# TRC_main1_0_0.net
KiCad netlist of a schematic drawn in EAGLE
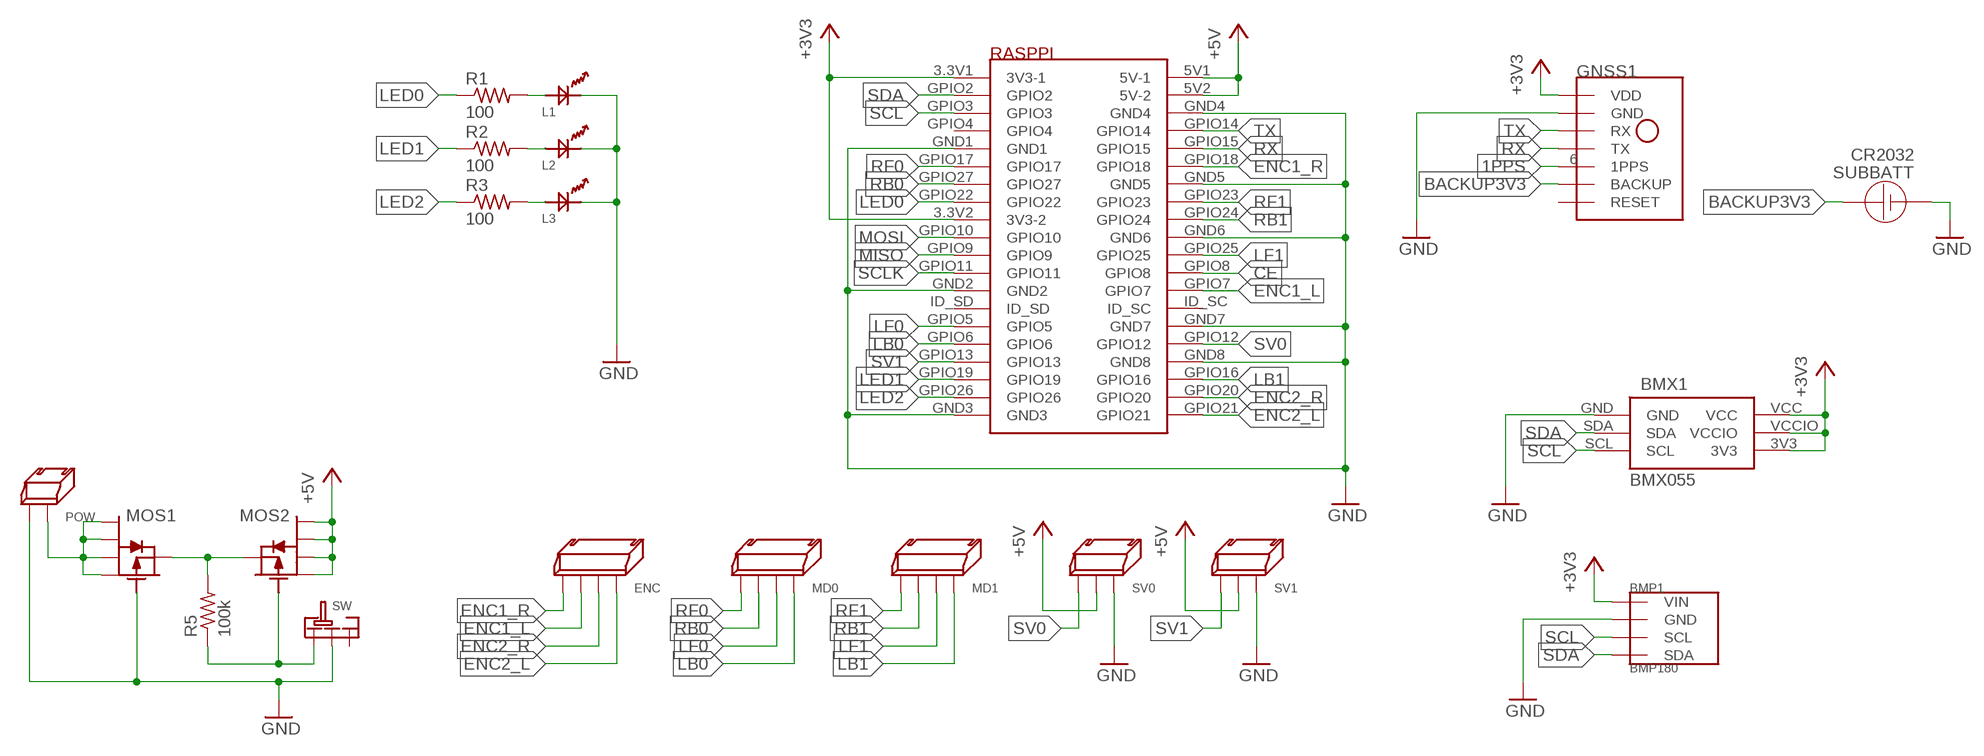
[diagram p0: schematic, sheet 1]

(export (version "E")
  (design (tool "Eeschema 10.0.6"))
  (components
    (comp (ref "BMP1")
      (value "BMP180")
      (footprint "eagle-import:GY-68")
      (libsource (lib "eagle-import") (part "BMP180"))
    )
    (comp (ref "BMX1")
      (value "BMX055")
      (footprint "eagle-import:BMX055")
      (libsource (lib "eagle-import") (part "BMX055"))
    )
    (comp (ref "ENC")
      (value "4PIN_SIDE")
      (footprint "eagle-import:4PIN_SIDE")
      (libsource (lib "eagle-import") (part "4PIN_SIDE"))
    )
    (comp (ref "GNSS1")
      (value "GYSFDMAXB")
      (footprint "eagle-import:GYSFDMAXB")
      (libsource (lib "eagle-import") (part "GYSFDMAXB"))
    )
    (comp (ref "L1")
      (value "OSXX1608C1A")
      (footprint "eagle-import:OSXX1608C1A")
      (libsource (lib "eagle-import") (part "OSXX1608C1A"))
    )
    (comp (ref "L2")
      (value "OSXX1608C1A")
      (footprint "eagle-import:OSXX1608C1A")
      (libsource (lib "eagle-import") (part "OSXX1608C1A"))
    )
    (comp (ref "L3")
      (value "OSXX1608C1A")
      (footprint "eagle-import:OSXX1608C1A")
      (libsource (lib "eagle-import") (part "OSXX1608C1A"))
    )
    (comp (ref "MD0")
      (value "4PIN_SIDE")
      (footprint "eagle-import:4PIN_SIDE")
      (libsource (lib "eagle-import") (part "4PIN_SIDE"))
    )
    (comp (ref "MD1")
      (value "4PIN_SIDE")
      (footprint "eagle-import:4PIN_SIDE")
      (libsource (lib "eagle-import") (part "4PIN_SIDE"))
    )
    (comp (ref "MOS1")
      (value "PCH_SSM6J808R")
      (footprint "eagle-import:SSM6J808R")
      (libsource (lib "eagle-import") (part "PCH_SSM6J808R"))
    )
    (comp (ref "MOS2")
      (value "PCH_SSM6J808R")
      (footprint "eagle-import:SSM6J808R")
      (libsource (lib "eagle-import") (part "PCH_SSM6J808R"))
    )
    (comp (ref "POW")
      (value "2PIN_SIDE")
      (footprint "eagle-import:2PIN_SIDE")
      (libsource (lib "eagle-import") (part "2PIN_SIDE"))
    )
    (comp (ref "R1")
      (value "100")
      (footprint "eagle-import:R0603")
      (libsource (lib "eagle-import") (part "R-US_R0603"))
    )
    (comp (ref "R2")
      (value "100")
      (footprint "eagle-import:R0603")
      (libsource (lib "eagle-import") (part "R-US_R0603"))
    )
    (comp (ref "R3")
      (value "100")
      (footprint "eagle-import:R0603")
      (libsource (lib "eagle-import") (part "R-US_R0603"))
    )
    (comp (ref "R5")
      (value "100k")
      (footprint "eagle-import:R0603")
      (libsource (lib "eagle-import") (part "R-US_R0603"))
    )
    (comp (ref "RASPPI")
      (value "RASPBERYPIZEROW")
      (footprint "eagle-import:RASPBERYPIZEROW")
      (libsource (lib "eagle-import") (part "RASPBERYPIZEROW"))
    )
    (comp (ref "SUBBATT")
      (value "CR2032")
      (footprint "eagle-import:CR2032")
      (libsource (lib "eagle-import") (part "CR2032"))
    )
    (comp (ref "SV0")
      (value "3PIN_SIDE")
      (footprint "eagle-import:3PIN_SIDE")
      (libsource (lib "eagle-import") (part "3PIN_SIDE"))
    )
    (comp (ref "SV1")
      (value "3PIN_SIDE")
      (footprint "eagle-import:3PIN_SIDE")
      (libsource (lib "eagle-import") (part "3PIN_SIDE"))
    )
    (comp (ref "SW")
      (value "SRIDE_SWITCH")
      (footprint "eagle-import:SRIDE_SWITCH")
      (libsource (lib "eagle-import") (part "SRIDE_SWITCH"))
    )
  )
  (nets
    (net (code "1") (name "+3V3") (class "Default")
      (node (ref "BMP1") (pin "P1") (pinfunction "VIN_P1") (pintype "bidirectional"))
      (node (ref "BMX1") (pin "3V3") (pinfunction "3V3_3V3") (pintype "power_in"))
      (node (ref "BMX1") (pin "VCC") (pinfunction "VCC_VCC") (pintype "power_in"))
      (node (ref "BMX1") (pin "VCCIO") (pinfunction "VCCIO_VCCIO") (pintype "power_in"))
      (node (ref "GNSS1") (pin "16") (pinfunction "VDD_16") (pintype "bidirectional"))
      (node (ref "RASPPI") (pin "3.3V1") (pinfunction "3V3-1_3.3V1") (pintype "bidirectional"))
      (node (ref "RASPPI") (pin "3.3V2") (pinfunction "3V3-2_3.3V2") (pintype "bidirectional"))
    )
    (net (code "2") (name "+5V") (class "Default")
      (node (ref "MOS2") (pin "1") (pinfunction "1_1") (pintype "bidirectional"))
      (node (ref "MOS2") (pin "2") (pinfunction "2_2") (pintype "bidirectional"))
      (node (ref "MOS2") (pin "5") (pinfunction "5_5") (pintype "bidirectional"))
      (node (ref "MOS2") (pin "6") (pinfunction "6_6") (pintype "bidirectional"))
      (node (ref "RASPPI") (pin "5V1") (pinfunction "5V-1_5V1") (pintype "bidirectional"))
      (node (ref "RASPPI") (pin "5V2") (pinfunction "5V-2_5V2") (pintype "bidirectional"))
      (node (ref "SV0") (pin "P$1") (pinfunction "P$1_P$1") (pintype "bidirectional"))
      (node (ref "SV1") (pin "P$1") (pinfunction "P$1_P$1") (pintype "bidirectional"))
    )
    (net (code "3") (name "1PPS") (class "Default")
      (node (ref "GNSS1") (pin "6") (pinfunction "1PPS_6") (pintype "bidirectional"))
    )
    (net (code "4") (name "BACKUP3V3") (class "Default")
      (node (ref "GNSS1") (pin "14") (pinfunction "BACKUP_14") (pintype "bidirectional"))
      (node (ref "SUBBATT") (pin "VCC") (pinfunction "VCC_VCC") (pintype "bidirectional"))
      (node (ref "SUBBATT") (pin "VCC2") (pinfunction "VCC_VCC2") (pintype "bidirectional"))
    )
    (net (code "5") (name "CE") (class "Default")
      (node (ref "RASPPI") (pin "GPIO8") (pinfunction "GPIO8_GPIO8") (pintype "bidirectional"))
    )
    (net (code "6") (name "ENC1_L") (class "Default")
      (node (ref "ENC") (pin "P$1") (pinfunction "P$1_P$1") (pintype "bidirectional"))
      (node (ref "RASPPI") (pin "GPIO7") (pinfunction "GPIO7_GPIO7") (pintype "bidirectional"))
    )
    (net (code "7") (name "ENC1_R") (class "Default")
      (node (ref "ENC") (pin "P$2") (pinfunction "P$2_P$2") (pintype "bidirectional"))
      (node (ref "RASPPI") (pin "GPIO18") (pinfunction "GPIO18_GPIO18") (pintype "bidirectional"))
    )
    (net (code "8") (name "ENC2_L") (class "Default")
      (node (ref "ENC") (pin "P$4") (pinfunction "P$4_P$4") (pintype "bidirectional"))
      (node (ref "RASPPI") (pin "GPIO21") (pinfunction "GPIO21_GPIO21") (pintype "bidirectional"))
    )
    (net (code "9") (name "ENC2_R") (class "Default")
      (node (ref "ENC") (pin "P$3") (pinfunction "P$3_P$3") (pintype "bidirectional"))
      (node (ref "RASPPI") (pin "GPIO20") (pinfunction "GPIO20_GPIO20") (pintype "bidirectional"))
    )
    (net (code "10") (name "GND") (class "Default")
      (node (ref "BMP1") (pin "P2") (pinfunction "GND_P2") (pintype "bidirectional"))
      (node (ref "BMX1") (pin "GND") (pinfunction "GND_GND") (pintype "power_in"))
      (node (ref "GNSS1") (pin "1") (pinfunction "GND_1") (pintype "bidirectional"))
      (node (ref "GNSS1") (pin "10") (pinfunction "GND_10") (pintype "bidirectional"))
      (node (ref "GNSS1") (pin "12") (pinfunction "GND_12") (pintype "bidirectional"))
      (node (ref "GNSS1") (pin "19") (pinfunction "GND_19") (pintype "bidirectional"))
      (node (ref "GNSS1") (pin "2") (pinfunction "GND_2") (pintype "bidirectional"))
      (node (ref "GNSS1") (pin "20") (pinfunction "GND_20") (pintype "bidirectional"))
      (node (ref "GNSS1") (pin "7") (pinfunction "GND_7") (pintype "bidirectional"))
      (node (ref "L1") (pin "CT") (pinfunction "CT_CT") (pintype "bidirectional"))
      (node (ref "L2") (pin "CT") (pinfunction "CT_CT") (pintype "bidirectional"))
      (node (ref "L3") (pin "CT") (pinfunction "CT_CT") (pintype "bidirectional"))
      (node (ref "MOS1") (pin "3") (pinfunction "3_3") (pintype "bidirectional"))
      (node (ref "POW") (pin "P$2") (pinfunction "P$2_P$2") (pintype "bidirectional"))
      (node (ref "RASPPI") (pin "GND1") (pinfunction "GND1_GND1") (pintype "bidirectional"))
      (node (ref "RASPPI") (pin "GND2") (pinfunction "GND2_GND2") (pintype "bidirectional"))
      (node (ref "RASPPI") (pin "GND3") (pinfunction "GND3_GND3") (pintype "bidirectional"))
      (node (ref "RASPPI") (pin "GND4") (pinfunction "GND4_GND4") (pintype "bidirectional"))
      (node (ref "RASPPI") (pin "GND5") (pinfunction "GND5_GND5") (pintype "bidirectional"))
      (node (ref "RASPPI") (pin "GND6") (pinfunction "GND6_GND6") (pintype "bidirectional"))
      (node (ref "RASPPI") (pin "GND7") (pinfunction "GND7_GND7") (pintype "bidirectional"))
      (node (ref "RASPPI") (pin "GND8") (pinfunction "GND8_GND8") (pintype "bidirectional"))
      (node (ref "SUBBATT") (pin "GND") (pinfunction "GND_GND") (pintype "bidirectional"))
      (node (ref "SV0") (pin "P$3") (pinfunction "P$3_P$3") (pintype "bidirectional"))
      (node (ref "SV1") (pin "P$3") (pinfunction "P$3_P$3") (pintype "bidirectional"))
      (node (ref "SW") (pin "LR") (pinfunction "LR_LR") (pintype "bidirectional"))
    )
    (net (code "11") (name "LB0") (class "Default")
      (node (ref "MD0") (pin "P$4") (pinfunction "P$4_P$4") (pintype "bidirectional"))
      (node (ref "RASPPI") (pin "GPIO6") (pinfunction "GPIO6_GPIO6") (pintype "bidirectional"))
    )
    (net (code "12") (name "LB1") (class "Default")
      (node (ref "MD1") (pin "P$4") (pinfunction "P$4_P$4") (pintype "bidirectional"))
      (node (ref "RASPPI") (pin "GPIO16") (pinfunction "GPIO16_GPIO16") (pintype "bidirectional"))
    )
    (net (code "13") (name "LED0") (class "Default")
      (node (ref "R1") (pin "1") (pinfunction "1_1") (pintype "passive"))
      (node (ref "RASPPI") (pin "GPIO22") (pinfunction "GPIO22_GPIO22") (pintype "bidirectional"))
    )
    (net (code "14") (name "LED1") (class "Default")
      (node (ref "R2") (pin "1") (pinfunction "1_1") (pintype "passive"))
      (node (ref "RASPPI") (pin "GPIO19") (pinfunction "GPIO19_GPIO19") (pintype "bidirectional"))
    )
    (net (code "15") (name "LED2") (class "Default")
      (node (ref "R3") (pin "1") (pinfunction "1_1") (pintype "passive"))
      (node (ref "RASPPI") (pin "GPIO26") (pinfunction "GPIO26_GPIO26") (pintype "bidirectional"))
    )
    (net (code "16") (name "LF0") (class "Default")
      (node (ref "MD0") (pin "P$3") (pinfunction "P$3_P$3") (pintype "bidirectional"))
      (node (ref "RASPPI") (pin "GPIO5") (pinfunction "GPIO5_GPIO5") (pintype "bidirectional"))
    )
    (net (code "17") (name "LF1") (class "Default")
      (node (ref "MD1") (pin "P$3") (pinfunction "P$3_P$3") (pintype "bidirectional"))
      (node (ref "RASPPI") (pin "GPIO25") (pinfunction "GPIO25_GPIO25") (pintype "bidirectional"))
    )
    (net (code "18") (name "MISO") (class "Default")
      (node (ref "RASPPI") (pin "GPIO9") (pinfunction "GPIO9_GPIO9") (pintype "bidirectional"))
    )
    (net (code "19") (name "MOSI") (class "Default")
      (node (ref "RASPPI") (pin "GPIO10") (pinfunction "GPIO10_GPIO10") (pintype "bidirectional"))
    )
    (net (code "20") (name "Net-(L1-PadAN)") (class "Default")
      (node (ref "L1") (pin "AN") (pinfunction "AN_AN") (pintype "bidirectional"))
      (node (ref "R1") (pin "2") (pinfunction "2_2") (pintype "passive"))
    )
    (net (code "21") (name "Net-(L2-PadAN)") (class "Default")
      (node (ref "L2") (pin "AN") (pinfunction "AN_AN") (pintype "bidirectional"))
      (node (ref "R2") (pin "2") (pinfunction "2_2") (pintype "passive"))
    )
    (net (code "22") (name "Net-(L3-PadAN)") (class "Default")
      (node (ref "L3") (pin "AN") (pinfunction "AN_AN") (pintype "bidirectional"))
      (node (ref "R3") (pin "2") (pinfunction "2_2") (pintype "passive"))
    )
    (net (code "23") (name "Net-(MOS1-Pad1)") (class "Default")
      (node (ref "MOS1") (pin "1") (pinfunction "1_1") (pintype "bidirectional"))
      (node (ref "MOS1") (pin "2") (pinfunction "2_2") (pintype "bidirectional"))
      (node (ref "MOS1") (pin "5") (pinfunction "5_5") (pintype "bidirectional"))
      (node (ref "MOS1") (pin "6") (pinfunction "6_6") (pintype "bidirectional"))
      (node (ref "POW") (pin "P$1") (pinfunction "P$1_P$1") (pintype "bidirectional"))
    )
    (net (code "24") (name "Net-(MOS1-Pad4)") (class "Default")
      (node (ref "MOS1") (pin "4") (pinfunction "4_4") (pintype "bidirectional"))
      (node (ref "MOS2") (pin "4") (pinfunction "4_4") (pintype "bidirectional"))
      (node (ref "R5") (pin "2") (pinfunction "2_2") (pintype "passive"))
    )
    (net (code "25") (name "Net-(MOS2-Pad3)") (class "Default")
      (node (ref "MOS2") (pin "3") (pinfunction "3_3") (pintype "bidirectional"))
      (node (ref "R5") (pin "1") (pinfunction "1_1") (pintype "passive"))
      (node (ref "SW") (pin "L") (pinfunction "L_L") (pintype "bidirectional"))
    )
    (net (code "26") (name "RB0") (class "Default")
      (node (ref "MD0") (pin "P$1") (pinfunction "P$1_P$1") (pintype "bidirectional"))
      (node (ref "RASPPI") (pin "GPIO27") (pinfunction "GPIO27_GPIO27") (pintype "bidirectional"))
    )
    (net (code "27") (name "RB1") (class "Default")
      (node (ref "MD1") (pin "P$1") (pinfunction "P$1_P$1") (pintype "bidirectional"))
      (node (ref "RASPPI") (pin "GPIO24") (pinfunction "GPIO24_GPIO24") (pintype "bidirectional"))
    )
    (net (code "28") (name "RF0") (class "Default")
      (node (ref "MD0") (pin "P$2") (pinfunction "P$2_P$2") (pintype "bidirectional"))
      (node (ref "RASPPI") (pin "GPIO17") (pinfunction "GPIO17_GPIO17") (pintype "bidirectional"))
    )
    (net (code "29") (name "RF1") (class "Default")
      (node (ref "MD1") (pin "P$2") (pinfunction "P$2_P$2") (pintype "bidirectional"))
      (node (ref "RASPPI") (pin "GPIO23") (pinfunction "GPIO23_GPIO23") (pintype "bidirectional"))
    )
    (net (code "30") (name "RX") (class "Default")
      (node (ref "GNSS1") (pin "5") (pinfunction "TX_5") (pintype "bidirectional"))
      (node (ref "RASPPI") (pin "GPIO15") (pinfunction "GPIO15_GPIO15") (pintype "bidirectional"))
    )
    (net (code "31") (name "SCL") (class "Default")
      (node (ref "BMP1") (pin "P3") (pinfunction "SCL_P3") (pintype "bidirectional"))
      (node (ref "BMX1") (pin "SCL") (pinfunction "SCL_SCL") (pintype "bidirectional"))
      (node (ref "RASPPI") (pin "GPIO3") (pinfunction "GPIO3_GPIO3") (pintype "bidirectional"))
    )
    (net (code "32") (name "SCLK") (class "Default")
      (node (ref "RASPPI") (pin "GPIO11") (pinfunction "GPIO11_GPIO11") (pintype "bidirectional"))
    )
    (net (code "33") (name "SDA") (class "Default")
      (node (ref "BMP1") (pin "P4") (pinfunction "SDA_P4") (pintype "bidirectional"))
      (node (ref "BMX1") (pin "SDA") (pinfunction "SDA_SDA") (pintype "bidirectional"))
      (node (ref "RASPPI") (pin "GPIO2") (pinfunction "GPIO2_GPIO2") (pintype "bidirectional"))
    )
    (net (code "34") (name "SV0") (class "Default")
      (node (ref "RASPPI") (pin "GPIO12") (pinfunction "GPIO12_GPIO12") (pintype "bidirectional"))
      (node (ref "SV0") (pin "P$2") (pinfunction "P$2_P$2") (pintype "bidirectional"))
    )
    (net (code "35") (name "SV1") (class "Default")
      (node (ref "RASPPI") (pin "GPIO13") (pinfunction "GPIO13_GPIO13") (pintype "bidirectional"))
      (node (ref "SV1") (pin "P$2") (pinfunction "P$2_P$2") (pintype "bidirectional"))
    )
    (net (code "36") (name "TX") (class "Default")
      (node (ref "GNSS1") (pin "3") (pinfunction "RX_3") (pintype "bidirectional"))
      (node (ref "RASPPI") (pin "GPIO14") (pinfunction "GPIO14_GPIO14") (pintype "bidirectional"))
    )
    (net (code "37") (name "unconnected-(GNSS1-RESET-Pad4)") (class "Default")
      (node (ref "GNSS1") (pin "4") (pinfunction "RESET_4") (pintype "bidirectional"))
    )
    (net (code "38") (name "unconnected-(RASPPI-PadGPIO4)") (class "Default")
      (node (ref "RASPPI") (pin "GPIO4") (pinfunction "GPIO4_GPIO4") (pintype "bidirectional"))
    )
    (net (code "39") (name "unconnected-(RASPPI-PadID_SC)") (class "Default")
      (node (ref "RASPPI") (pin "ID_SC") (pinfunction "ID_SC_ID_SC") (pintype "bidirectional"))
    )
    (net (code "40") (name "unconnected-(RASPPI-PadID_SD)") (class "Default")
      (node (ref "RASPPI") (pin "ID_SD") (pinfunction "ID_SD_ID_SD") (pintype "bidirectional"))
    )
    (net (code "41") (name "unconnected-(SW-PadR)") (class "Default")
      (node (ref "SW") (pin "R") (pinfunction "R_R") (pintype "bidirectional"))
    )
  )
)
